# ROM.net
KiCad netlist of a schematic drawn in Altium Designer
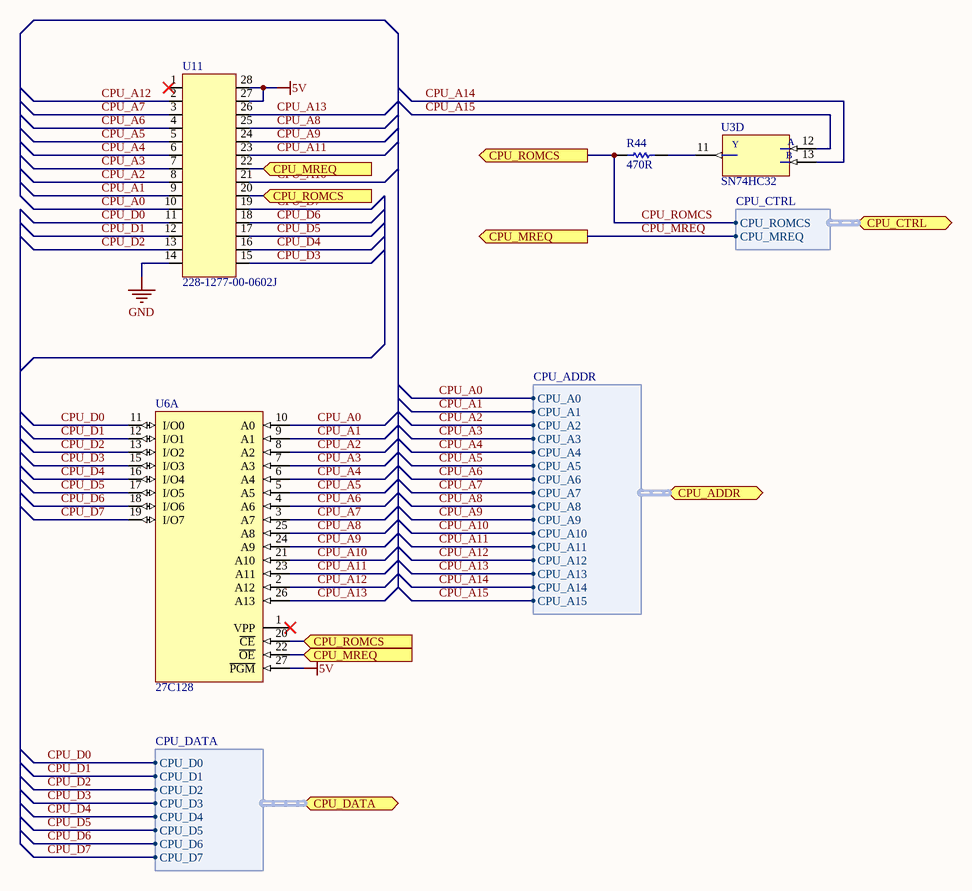
[diagram p0: ROM.SchDoc]

(export (version "E")
  (design (tool "Eeschema 10.0.6"))
  (components
    (comp (ref "R44") (value "470R") (footprint "0805") (libsource (lib "Basic") (part "Resistor")))
    (comp (ref "U3")
      (value "SN74HC32")
      (footprint "SOIC14")
      (description "Quadruple 2-Input Positive-OR Gates")
      (libsource (lib "Texas Instruments") (part "SN74HC32"))
    )
    (comp (ref "U6")
      (value "27C128")
      (footprint "PDIP28")
      (description "128K (16K x 8) CMOS EPROM")
      (libsource (lib "Microchip") (part "27C128"))
    )
    (comp (ref "U11")
      (value "228-1277-00-0602J")
      (footprint "228-1277-00-0602J")
      (description "DIP Sockets - 28 Pins")
      (libsource (lib "3M") (part "228-1277-00-0602J"))
    )
  )
  (nets
    (net (code "4") (name "/CPU_A0") (class "Default")
      (node (ref "U11") (pin "10") (pinfunction "10_10") (pintype "passive"))
      (node (ref "U6") (pin "10") (pinfunction "A0_10") (pintype "input"))
    )
    (net (code "5") (name "/CPU_A1") (class "Default")
      (node (ref "U11") (pin "9") (pinfunction "9_9") (pintype "passive"))
      (node (ref "U6") (pin "9") (pinfunction "A1_9") (pintype "input"))
    )
    (net (code "6") (name "/CPU_A2") (class "Default")
      (node (ref "U11") (pin "8") (pinfunction "8_8") (pintype "passive"))
      (node (ref "U6") (pin "8") (pinfunction "A2_8") (pintype "input"))
    )
    (net (code "7") (name "/CPU_A3") (class "Default")
      (node (ref "U11") (pin "7") (pinfunction "7_7") (pintype "passive"))
      (node (ref "U6") (pin "7") (pinfunction "A3_7") (pintype "input"))
    )
    (net (code "8") (name "/CPU_A4") (class "Default")
      (node (ref "U11") (pin "6") (pinfunction "6_6") (pintype "passive"))
      (node (ref "U6") (pin "6") (pinfunction "A4_6") (pintype "input"))
    )
    (net (code "9") (name "/CPU_A5") (class "Default")
      (node (ref "U11") (pin "5") (pinfunction "5_5") (pintype "passive"))
      (node (ref "U6") (pin "5") (pinfunction "A5_5") (pintype "input"))
    )
    (net (code "10") (name "/CPU_A6") (class "Default")
      (node (ref "U11") (pin "4") (pinfunction "4_4") (pintype "passive"))
      (node (ref "U6") (pin "4") (pinfunction "A6_4") (pintype "input"))
    )
    (net (code "11") (name "/CPU_A7") (class "Default")
      (node (ref "U11") (pin "3") (pinfunction "3_3") (pintype "passive"))
      (node (ref "U6") (pin "3") (pinfunction "A7_3") (pintype "input"))
    )
    (net (code "12") (name "/CPU_A8") (class "Default")
      (node (ref "U11") (pin "25") (pinfunction "25_25") (pintype "passive"))
      (node (ref "U6") (pin "25") (pinfunction "A8_25") (pintype "input"))
    )
    (net (code "13") (name "/CPU_A9") (class "Default")
      (node (ref "U11") (pin "24") (pinfunction "24_24") (pintype "passive"))
      (node (ref "U6") (pin "24") (pinfunction "A9_24") (pintype "input"))
    )
    (net (code "14") (name "/CPU_A10") (class "Default")
      (node (ref "U11") (pin "21") (pinfunction "21_21") (pintype "passive"))
      (node (ref "U6") (pin "21") (pinfunction "A10_21") (pintype "input"))
    )
    (net (code "15") (name "/CPU_A11") (class "Default")
      (node (ref "U11") (pin "23") (pinfunction "23_23") (pintype "passive"))
      (node (ref "U6") (pin "23") (pinfunction "A11_23") (pintype "input"))
    )
    (net (code "16") (name "/CPU_A12") (class "Default")
      (node (ref "U11") (pin "2") (pinfunction "2_2") (pintype "passive"))
      (node (ref "U6") (pin "2") (pinfunction "A12_2") (pintype "input"))
    )
    (net (code "17") (name "/CPU_A13") (class "Default")
      (node (ref "U11") (pin "26") (pinfunction "26_26") (pintype "passive"))
      (node (ref "U6") (pin "26") (pinfunction "A13_26") (pintype "input"))
    )
    (net (code "18") (name "/CPU_A14") (class "Default")
      (node (ref "U3") (pin "13") (pinfunction "B_13") (pintype "input"))
    )
    (net (code "19") (name "/CPU_A15") (class "Default")
      (node (ref "U3") (pin "12") (pinfunction "A_12") (pintype "input"))
    )
    (net (code "20") (name "/CPU_D0") (class "Default")
      (node (ref "U11") (pin "11") (pinfunction "11_11") (pintype "passive"))
      (node (ref "U6") (pin "11") (pinfunction "I/O0_11") (pintype "bidirectional"))
    )
    (net (code "21") (name "/CPU_D1") (class "Default")
      (node (ref "U11") (pin "12") (pinfunction "12_12") (pintype "passive"))
      (node (ref "U6") (pin "12") (pinfunction "I/O1_12") (pintype "bidirectional"))
    )
    (net (code "22") (name "/CPU_D2") (class "Default")
      (node (ref "U11") (pin "13") (pinfunction "13_13") (pintype "passive"))
      (node (ref "U6") (pin "13") (pinfunction "I/O2_13") (pintype "bidirectional"))
    )
    (net (code "23") (name "/CPU_D3") (class "Default")
      (node (ref "U11") (pin "15") (pinfunction "15_15") (pintype "passive"))
      (node (ref "U6") (pin "15") (pinfunction "I/O3_15") (pintype "bidirectional"))
    )
    (net (code "24") (name "/CPU_D4") (class "Default")
      (node (ref "U11") (pin "16") (pinfunction "16_16") (pintype "passive"))
      (node (ref "U6") (pin "16") (pinfunction "I/O4_16") (pintype "bidirectional"))
    )
    (net (code "25") (name "/CPU_D5") (class "Default")
      (node (ref "U11") (pin "17") (pinfunction "17_17") (pintype "passive"))
      (node (ref "U6") (pin "17") (pinfunction "I/O5_17") (pintype "bidirectional"))
    )
    (net (code "26") (name "/CPU_D6") (class "Default")
      (node (ref "U11") (pin "18") (pinfunction "18_18") (pintype "passive"))
      (node (ref "U6") (pin "18") (pinfunction "I/O6_18") (pintype "bidirectional"))
    )
    (net (code "27") (name "/CPU_D7") (class "Default")
      (node (ref "U11") (pin "19") (pinfunction "19_19") (pintype "passive"))
      (node (ref "U6") (pin "19") (pinfunction "I/O7_19") (pintype "bidirectional"))
    )
    (net (code "28") (name "/CPU_MREQ") (class "Default")
      (node (ref "U11") (pin "22") (pinfunction "22_22") (pintype "passive"))
      (node (ref "U6") (pin "22") (pinfunction "~{OE}_22") (pintype "input"))
    )
    (net (code "29") (name "/CPU_ROMCS") (class "Default")
      (node (ref "R44") (pin "2") (pinfunction "2_2") (pintype "passive"))
      (node (ref "U11") (pin "20") (pinfunction "20_20") (pintype "passive"))
      (node (ref "U6") (pin "20") (pinfunction "~{CE}_20") (pintype "input"))
    )
    (net (code "33") (name "5V") (class "Default")
      (node (ref "U11") (pin "27") (pinfunction "27_27") (pintype "passive"))
      (node (ref "U11") (pin "28") (pinfunction "28_28") (pintype "passive"))
      (node (ref "U6") (pin "27") (pinfunction "~{PGM}_27") (pintype "input"))
    )
    (net (code "34") (name "GND") (class "Default")
      (node (ref "U11") (pin "14") (pinfunction "14_14") (pintype "passive"))
    )
    (net (code "35") (name "Net-(U3D-Y)") (class "Default")
      (node (ref "R44") (pin "1") (pinfunction "1_1") (pintype "passive"))
      (node (ref "U3") (pin "11") (pinfunction "Y_11") (pintype "output"))
    )
    (net (code "36") (name "unconnected-(U6A-VPP-Pad1)") (class "Default")
      (node (ref "U6") (pin "1") (pinfunction "VPP_1") (pintype "power_in+no_connect"))
    )
    (net (code "37") (name "unconnected-(U11-Pad1)") (class "Default")
      (node (ref "U11") (pin "1") (pinfunction "1_1") (pintype "passive+no_connect"))
    )
  )
)
